# Servo_control_module.net
KiCad netlist of a schematic drawn in Altium Designer
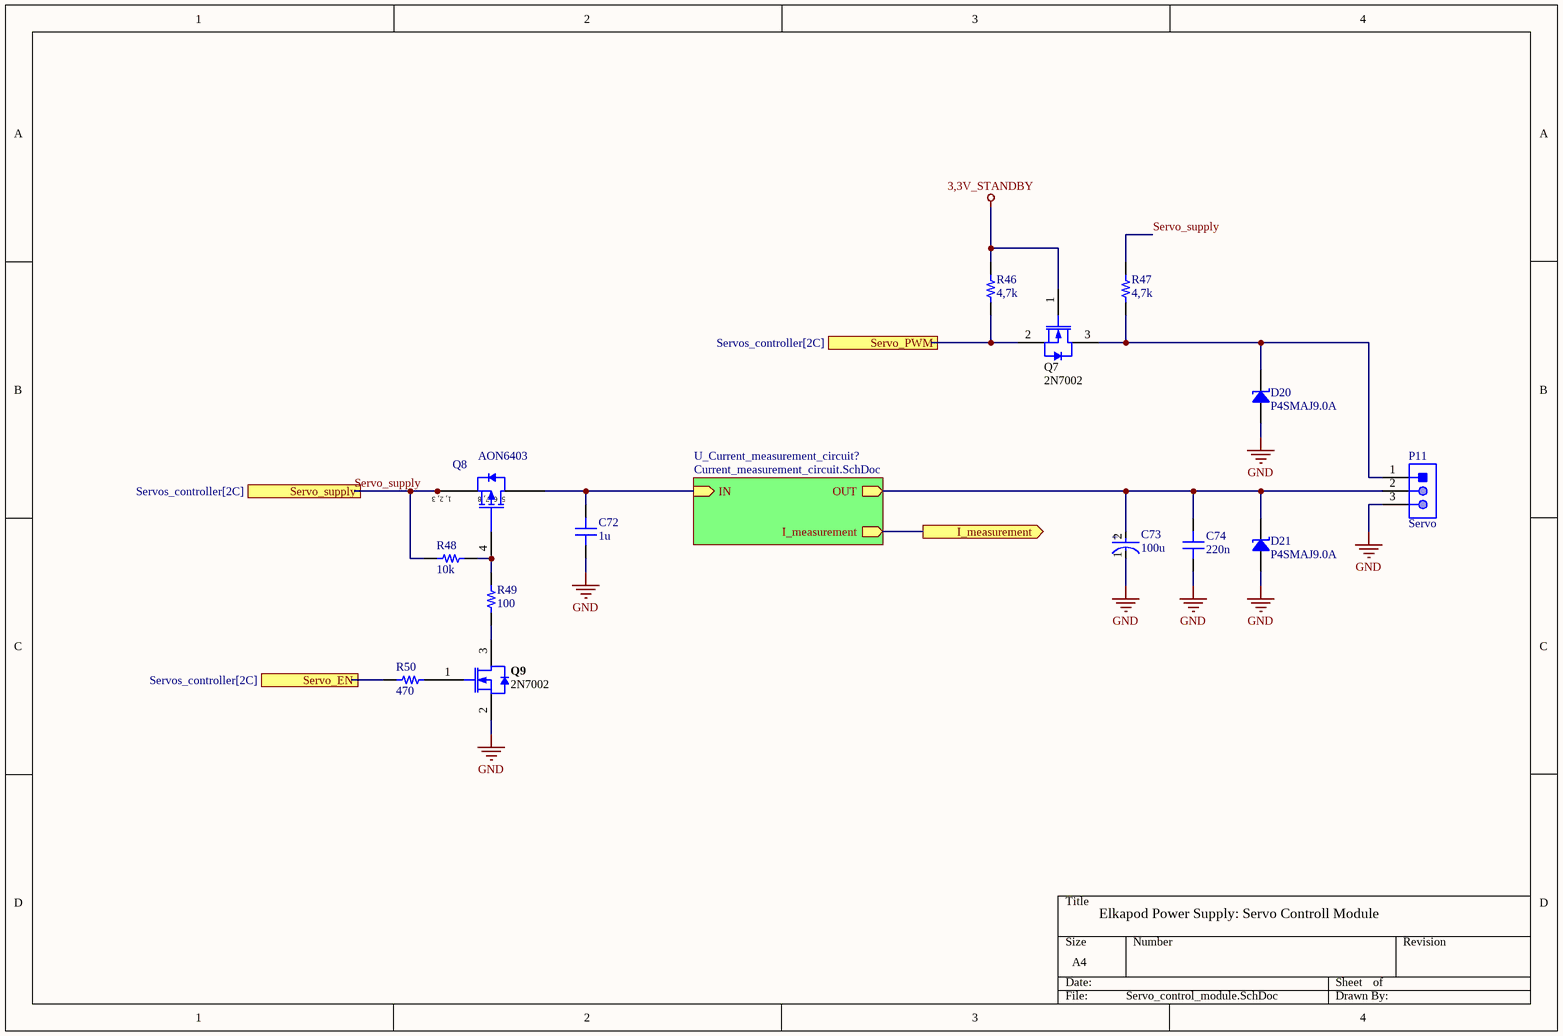
[diagram p0: Servo_control_module.SchDoc]

(export (version "E")
  (design (tool "Eeschema 10.0.6"))
  (components
    (comp (ref "C72")
      (value "1u")
      (footprint "CAP 0603_1608")
      (description "CAP CER 1uF 16V X5R 0603")
      (fields (field (name "PART NUMBER") "C0603C272F3GAC7867") (field (name "MANUFACTURER") "KEMET"))
      (libsource (lib "Celestial Altium Library - altium_library") (part "Capacitor"))
    )
    (comp (ref "C73")
      (value "100u")
      (footprint "FP-FKE-MFG")
      (description "CAP ALUM 100UF 20% 25V SMD")
      (fields (field (name "TOLERANCE") "20%") (field (name "VOLTAGE") "25V"))
      (libsource (lib "Altium Content Vault") (part "203bc49f2ac43e59fd269a8c329ed05"))
    )
    (comp (ref "C74")
      (value "220n")
      (footprint "CAP 0603_1608")
      (description "CAP CER 220nF 25V X5R 0603")
      (fields (field (name "PART NUMBER") "C0603C272F3GAC7867") (field (name "MANUFACTURER") "KEMET"))
      (libsource (lib "Celestial Altium Library - altium_library") (part "Capacitor"))
    )
    (comp (ref "D20")
      (value "P4SMAJ9.0A")
      (footprint "DO214AC SMA")
      (description "TVS DIODE 9VDC DO214AC")
      (libsource (lib "Celestial Altium Library - altium_library") (part "DIODE TVS UNI"))
    )
    (comp (ref "D21")
      (value "P4SMAJ9.0A")
      (footprint "DO214AC SMA")
      (description "TVS DIODE 9VDC DO214AC")
      (libsource (lib "Celestial Altium Library - altium_library") (part "DIODE TVS UNI"))
    )
    (comp (ref "P11")
      (value "Servo")
      (footprint "MOLX-22-23-2031_V")
      (description "Male Header, Pitch 2.54 mm, 1 x 3 Position, Height 8.18 mm, Tail Length 3.56 mm, RoHS, Bulk")
      (fields (field (name "MANUFACTURER") "Molex"))
      (libsource (lib "Altium Content Vault") (part "CN-1P-M-R3"))
    )
    (comp (ref "Q7")
      (value "2N7002")
      (footprint "INF-PG-SOT23_M")
      (fields (field (name "MANUFACTURER") "Infineon"))
      (libsource (lib "Altium Content Vault") (part "INF-NDMOS-GSD-3"))
    )
    (comp (ref "Q8")
      (value "AON6403")
      (footprint "DFN5x6")
      (description "P-MOSFET; 67A; 30V; DFN5x6")
      (libsource (lib "My_transistors") (part "AON6403"))
    )
    (comp (ref "Q9")
      (value "2N7002")
      (footprint "INF-PG-SOT23_M")
      (fields (field (name "MANUFACTURER") "Infineon"))
      (libsource (lib "Altium Content Vault") (part "INF-NDMOS-GSD-3"))
    )
    (comp (ref "R46")
      (value "4,7k")
      (footprint "RES 0603_1608")
      (description "RES 4,7K OHM 1% 0,1W 0603")
      (fields
        (field (name "PART NUMBER") "RNCS0603BKE10K0")
        (field (name "MANUFACTURER") "Stackpole Electronics Inc")
      )
      (libsource (lib "Celestial Altium Library - altium_library") (part "Resistor"))
    )
    (comp (ref "R47")
      (value "4,7k")
      (footprint "RES 0603_1608")
      (description "RES 4,7K OHM 1% 0,1W 0603")
      (fields
        (field (name "PART NUMBER") "RNCS0603BKE10K0")
        (field (name "MANUFACTURER") "Stackpole Electronics Inc")
      )
      (libsource (lib "Celestial Altium Library - altium_library") (part "Resistor"))
    )
    (comp (ref "R48")
      (value "10k")
      (footprint "RES 0603_1608")
      (description "RES 10K OHM 1% 0,1W 0603")
      (fields
        (field (name "PART NUMBER") "RNCS0603BKE10K0")
        (field (name "MANUFACTURER") "Stackpole Electronics Inc")
      )
      (libsource (lib "Celestial Altium Library - altium_library") (part "Resistor"))
    )
    (comp (ref "R49")
      (value "100")
      (footprint "RES 0603_1608")
      (description "RES 100 OHM 1% 0,1W 0603")
      (fields
        (field (name "PART NUMBER") "RNCS0603BKE10K0")
        (field (name "MANUFACTURER") "Stackpole Electronics Inc")
      )
      (libsource (lib "Celestial Altium Library - altium_library") (part "Resistor"))
    )
    (comp (ref "R50")
      (value "470")
      (footprint "RES 0603_1608")
      (description "RES 470 OHM 1% 0,1W 0603")
      (fields
        (field (name "PART NUMBER") "RNCS0603BKE10K0")
        (field (name "MANUFACTURER") "Stackpole Electronics Inc")
      )
      (libsource (lib "Celestial Altium Library - altium_library") (part "Resistor"))
    )
  )
  (nets
    (net (code "1") (name "/IN") (class "Default")
      (node (ref "C72") (pin "2") (pinfunction "2_2") (pintype "passive"))
      (node (ref "Q8") (pin "5-6-7-8") (pinfunction "D_5-6-7-8") (pintype "passive"))
    )
    (net (code "3") (name "/OUT") (class "Default")
      (node (ref "C73") (pin "2") (pinfunction "A_2") (pintype "passive"))
      (node (ref "C74") (pin "1") (pinfunction "1_1") (pintype "passive"))
      (node (ref "D21") (pin "2") (pinfunction "2_2") (pintype "passive"))
      (node (ref "P11") (pin "2") (pinfunction "2_2") (pintype "passive"))
    )
    (net (code "4") (name "/Servo_EN") (class "Default")
      (node (ref "R50") (pin "2") (pinfunction "2_2") (pintype "passive"))
    )
    (net (code "5") (name "/Servo_PWM") (class "Default")
      (node (ref "Q7") (pin "2") (pinfunction "SOURCE_2") (pintype "passive"))
      (node (ref "R46") (pin "1") (pinfunction "1_1") (pintype "passive"))
    )
    (net (code "6") (name "/Servo_supply") (class "Default")
      (node (ref "Q8") (pin "1") (pinfunction "S_1") (pintype "passive"))
      (node (ref "Q8") (pin "2") (pinfunction "S_2") (pintype "passive"))
      (node (ref "Q8") (pin "3") (pinfunction "S_3") (pintype "passive"))
      (node (ref "R47") (pin "2") (pinfunction "2_2") (pintype "passive"))
      (node (ref "R48") (pin "1") (pinfunction "1_1") (pintype "passive"))
    )
    (net (code "7") (name "3,3V_STANDBY") (class "Default")
      (node (ref "Q7") (pin "1") (pinfunction "GATE_1") (pintype "passive"))
      (node (ref "R46") (pin "2") (pinfunction "2_2") (pintype "passive"))
    )
    (net (code "8") (name "GND") (class "Default")
      (node (ref "C72") (pin "1") (pinfunction "1_1") (pintype "passive"))
      (node (ref "C73") (pin "1") (pinfunction "C_1") (pintype "passive"))
      (node (ref "C74") (pin "2") (pinfunction "2_2") (pintype "passive"))
      (node (ref "D20") (pin "1") (pinfunction "1_1") (pintype "passive"))
      (node (ref "D21") (pin "1") (pinfunction "1_1") (pintype "passive"))
      (node (ref "P11") (pin "3") (pinfunction "3_3") (pintype "passive"))
      (node (ref "Q9") (pin "2") (pinfunction "SOURCE_2") (pintype "passive"))
    )
    (net (code "9") (name "Net-(Q7-DRAIN)") (class "Default")
      (node (ref "D20") (pin "2") (pinfunction "2_2") (pintype "passive"))
      (node (ref "P11") (pin "1") (pinfunction "1_1") (pintype "passive"))
      (node (ref "Q7") (pin "3") (pinfunction "DRAIN_3") (pintype "passive"))
      (node (ref "R47") (pin "1") (pinfunction "1_1") (pintype "passive"))
    )
    (net (code "10") (name "Net-(Q8-G)") (class "Default")
      (node (ref "Q8") (pin "4") (pinfunction "G_4") (pintype "passive"))
      (node (ref "R48") (pin "2") (pinfunction "2_2") (pintype "passive"))
      (node (ref "R49") (pin "2") (pinfunction "2_2") (pintype "passive"))
    )
    (net (code "11") (name "Net-(Q9-DRAIN)") (class "Default")
      (node (ref "Q9") (pin "3") (pinfunction "DRAIN_3") (pintype "passive"))
      (node (ref "R49") (pin "1") (pinfunction "1_1") (pintype "passive"))
    )
    (net (code "12") (name "Net-(Q9-GATE)") (class "Default")
      (node (ref "Q9") (pin "1") (pinfunction "GATE_1") (pintype "passive"))
      (node (ref "R50") (pin "1") (pinfunction "1_1") (pintype "passive"))
    )
  )
)
